# v1m.net
KiCad netlist of a schematic drawn in EAGLE
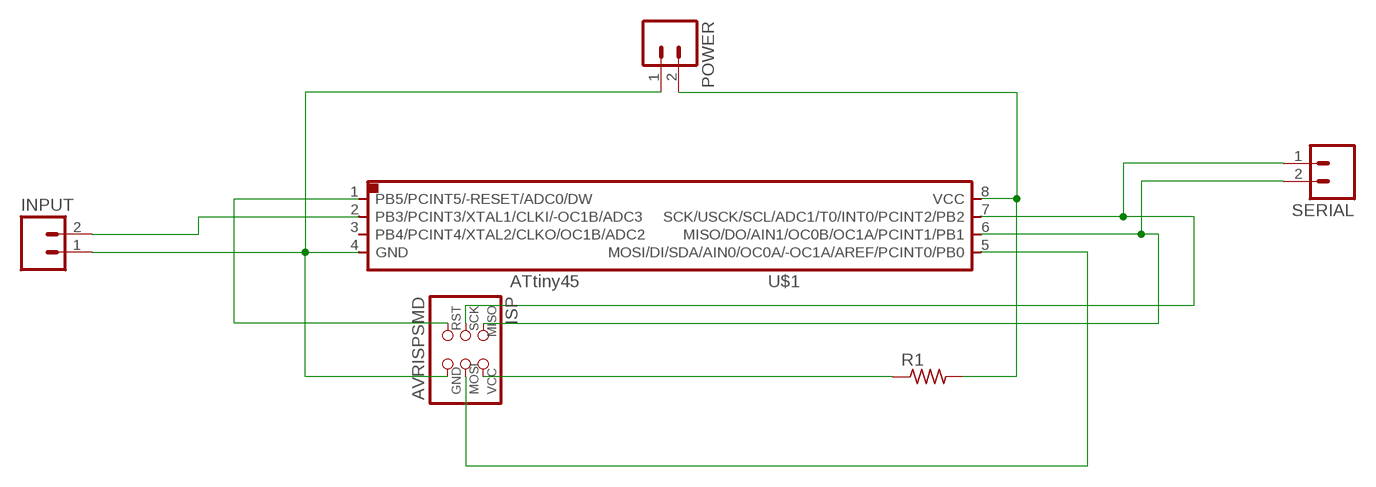
[diagram p0: schematic, sheet 1]

(export (version "E")
  (design (tool "Eeschema 10.0.6"))
  (components
    (comp (ref "INPUT")
      (value "M02JUST2PADS")
      (footprint "eagle-import:JST-2-SMD-VERT")
      (libsource (lib "eagle-import") (part "M02JUST2PADS"))
    )
    (comp (ref "ISP")
      (value "AVRISPSMD")
      (footprint "eagle-import:2X03SMD")
      (libsource (lib "eagle-import") (part "AVRISPSMD"))
    )
    (comp (ref "POWER")
      (value "M02JUST2PADS")
      (footprint "eagle-import:JST-2-SMD-VERT")
      (libsource (lib "eagle-import") (part "M02JUST2PADS"))
    )
    (comp (ref "R1")
      (value "RES-US1206")
      (footprint "eagle-import:R1206")
      (libsource (lib "eagle-import") (part "RES-US1206"))
    )
    (comp (ref "SERIAL")
      (value "M02JUST2PADS")
      (footprint "eagle-import:JST-2-SMD-VERT")
      (libsource (lib "eagle-import") (part "M02JUST2PADS"))
    )
    (comp (ref "U$1")
      (value "ATTINY45SI")
      (footprint "eagle-import:SOIC8")
      (libsource (lib "eagle-import") (part "ATTINY45SI"))
    )
  )
  (nets
    (net (code "1") (name "Net-(ISP-GND)") (class "Default")
      (node (ref "INPUT") (pin "1") (pinfunction "1_1") (pintype "passive"))
      (node (ref "ISP") (pin "6") (pinfunction "GND_6") (pintype "passive"))
      (node (ref "POWER") (pin "1") (pinfunction "1_1") (pintype "passive"))
      (node (ref "U$1") (pin "4") (pinfunction "GND_4") (pintype "bidirectional"))
    )
    (net (code "2") (name "Net-(ISP-MISO)") (class "Default")
      (node (ref "ISP") (pin "1") (pinfunction "MISO_1") (pintype "passive"))
      (node (ref "SERIAL") (pin "2") (pinfunction "2_2") (pintype "passive"))
      (node (ref "U$1") (pin "6") (pinfunction "MISO/DO/AIN1/OC0B/OC1A/PCINT1/PB1_6") (pintype "bidirectional"))
    )
    (net (code "3") (name "Net-(ISP-MOSI)") (class "Default")
      (node (ref "ISP") (pin "4") (pinfunction "MOSI_4") (pintype "passive"))
      (node (ref "U$1") (pin "5") (pinfunction "MOSI/DI/SDA/AIN0/OC0A/-OC1A/AREF/PCINT0/PB0_5") (pintype "bidirectional"))
    )
    (net (code "4") (name "Net-(ISP-RST)") (class "Default")
      (node (ref "ISP") (pin "5") (pinfunction "RST_5") (pintype "passive"))
      (node (ref "U$1") (pin "1") (pinfunction "PB5/PCINT5/-RESET/ADC0/DW_1") (pintype "bidirectional"))
    )
    (net (code "5") (name "Net-(ISP-SCK)") (class "Default")
      (node (ref "ISP") (pin "3") (pinfunction "SCK_3") (pintype "passive"))
      (node (ref "SERIAL") (pin "1") (pinfunction "1_1") (pintype "passive"))
      (node (ref "U$1") (pin "7") (pinfunction "SCK/USCK/SCL/ADC1/T0/INT0/PCINT2/PB2_7") (pintype "bidirectional"))
    )
    (net (code "6") (name "Net-(ISP-VCC)") (class "Default")
      (node (ref "ISP") (pin "2") (pinfunction "VCC_2") (pintype "passive"))
      (node (ref "R1") (pin "1") (pinfunction "1_1") (pintype "passive"))
    )
    (net (code "7") (name "Net-(U$1-PB3{slash}PCINT3{slash}XTAL1{slash}CLKI{slash}-OC1B{slash}ADC3)") (class "Default")
      (node (ref "INPUT") (pin "2") (pinfunction "2_2") (pintype "passive"))
      (node (ref "U$1") (pin "2") (pinfunction "PB3/PCINT3/XTAL1/CLKI/-OC1B/ADC3_2") (pintype "bidirectional"))
    )
    (net (code "8") (name "Net-(U$1-VCC)") (class "Default")
      (node (ref "POWER") (pin "2") (pinfunction "2_2") (pintype "passive"))
      (node (ref "R1") (pin "2") (pinfunction "2_2") (pintype "passive"))
      (node (ref "U$1") (pin "8") (pinfunction "VCC_8") (pintype "bidirectional"))
    )
    (net (code "9") (name "unconnected-(U$1-PB4{slash}PCINT4{slash}XTAL2{slash}CLKO{slash}OC1B{slash}ADC2-Pad3)") (class "Default")
      (node (ref "U$1") (pin "3") (pinfunction "PB4/PCINT4/XTAL2/CLKO/OC1B/ADC2_3") (pintype "bidirectional"))
    )
  )
)
